# Opioid_-_IO_-_rev_A0.net
KiCad netlist of a schematic drawn in Altium Designer
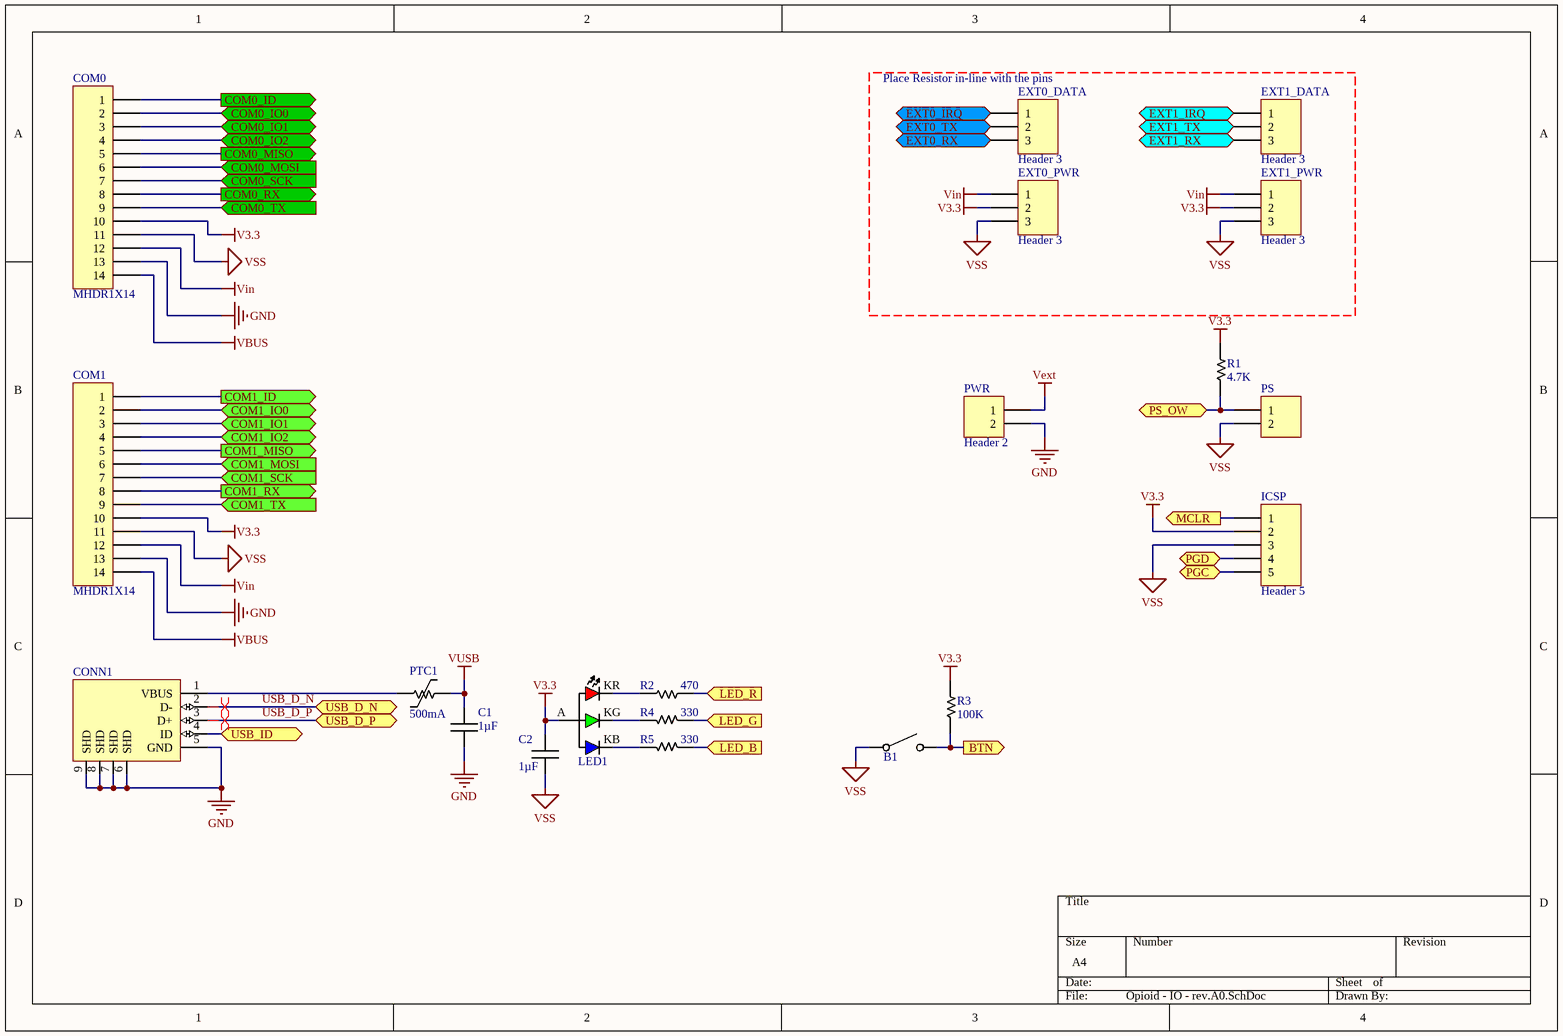
[diagram p0: Opioid - IO - rev.A0.SchDoc]

(export (version "E")
  (design (tool "Eeschema 10.0.6"))
  (components
    (comp (ref "B1")
      (value "Tact Button NO")
      (footprint "Tact TH 4pin 6×6mm")
      (libsource (lib "Megaxone") (part "Tact Button NO"))
    )
    (comp (ref "C1") (value "1µF") (footprint "CAPC1608N") (libsource (lib "Megaxone") (part "Capacitor")))
    (comp (ref "C2") (value "1µF") (footprint "CAPC1608N") (libsource (lib "Megaxone") (part "Capacitor")))
    (comp (ref "COM0")
      (value "MHDR1X14")
      (footprint "MHDR1X14")
      (description "Header, 14-Pin")
      (fields (field (name "PUBLISHER") "Altium Limited"))
      (libsource (lib "Miscellaneous Connectors") (part "MHDR1X14"))
    )
    (comp (ref "COM1")
      (value "MHDR1X14")
      (footprint "MHDR1X14")
      (description "Header, 14-Pin")
      (fields (field (name "PUBLISHER") "Altium Limited"))
      (libsource (lib "Miscellaneous Connectors") (part "MHDR1X14"))
    )
    (comp (ref "CONN1")
      (value "USB-Conn Mini-B SMD")
      (footprint "440478")
      (libsource (lib "Megaxone") (part "USB-Conn Mini-B SMD"))
    )
    (comp (ref "EXT0_DATA")
      (value "Header 3")
      (footprint "HDR1X3")
      (description "Header, 3-Pin")
      (fields (field (name "PUBLISHER") "Altium Limited"))
      (libsource (lib "Miscellaneous Connectors") (part "Header 3"))
    )
    (comp (ref "EXT0_PWR")
      (value "Header 3")
      (footprint "HDR1X3")
      (description "Header, 3-Pin")
      (fields (field (name "PUBLISHER") "Altium Limited"))
      (libsource (lib "Miscellaneous Connectors") (part "Header 3"))
    )
    (comp (ref "EXT1_DATA")
      (value "Header 3")
      (footprint "HDR1X3")
      (description "Header, 3-Pin")
      (fields (field (name "PUBLISHER") "Altium Limited"))
      (libsource (lib "Miscellaneous Connectors") (part "Header 3"))
    )
    (comp (ref "EXT1_PWR")
      (value "Header 3")
      (footprint "HDR1X3")
      (description "Header, 3-Pin")
      (fields (field (name "PUBLISHER") "Altium Limited"))
      (libsource (lib "Miscellaneous Connectors") (part "Header 3"))
    )
    (comp (ref "ICSP")
      (value "Header 5")
      (footprint "HDR1X5")
      (description "Header, 5-Pin")
      (fields (field (name "PUBLISHER") "Altium Limited"))
      (libsource (lib "Miscellaneous Connectors") (part "Header 5"))
    )
    (comp (ref "LED1")
      (value "LED RGB common A")
      (footprint "LED 3528m")
      (libsource (lib "Megaxone") (part "LED RGB common A"))
    )
    (comp (ref "PS")
      (value "MHDR1X2")
      (footprint "MHDR1X2")
      (description "Header, 2-Pin")
      (fields (field (name "PUBLISHER") "Altium Limited"))
      (libsource (lib "Miscellaneous Connectors") (part "MHDR1X2"))
    )
    (comp (ref "PTC1") (value "500mA") (footprint "RESC3225N") (libsource (lib "Megaxone") (part "PTC")))
    (comp (ref "PWR")
      (value "Header 2")
      (footprint "HDR1X2")
      (description "Header, 2-Pin")
      (fields (field (name "PUBLISHER") "Altium Limited"))
      (libsource (lib "Miscellaneous Connectors") (part "Header 2"))
    )
    (comp (ref "R1") (value "4.7K") (footprint "RESC1608N") (libsource (lib "") (part "Resistor_1")))
    (comp (ref "R2") (value "470") (footprint "RESC1608N") (libsource (lib "Megaxone") (part "Resistor")))
    (comp (ref "R3") (value "100K") (footprint "RESC1608N") (libsource (lib "") (part "Resistor_1")))
    (comp (ref "R4") (value "330") (footprint "RESC1608N") (libsource (lib "") (part "Resistor_1")))
    (comp (ref "R5") (value "330") (footprint "RESC1608N") (libsource (lib "") (part "Resistor_1")))
  )
  (nets
    (net (code "1") (name "/BTN") (class "Default")
      (node (ref "B1") (pin "2") (pinfunction "2_2") (pintype "passive"))
      (node (ref "R3") (pin "1") (pinfunction "1_1") (pintype "passive"))
    )
    (net (code "2") (name "/COM0_ID") (class "Default")
      (node (ref "COM0") (pin "1") (pinfunction "1_1") (pintype "passive"))
    )
    (net (code "3") (name "/COM0_IO0") (class "Default")
      (node (ref "COM0") (pin "2") (pinfunction "2_2") (pintype "passive"))
    )
    (net (code "4") (name "/COM0_IO1") (class "Default")
      (node (ref "COM0") (pin "3") (pinfunction "3_3") (pintype "passive"))
    )
    (net (code "5") (name "/COM0_IO2") (class "Default")
      (node (ref "COM0") (pin "4") (pinfunction "4_4") (pintype "passive"))
    )
    (net (code "6") (name "/COM0_MISO") (class "Default")
      (node (ref "COM0") (pin "5") (pinfunction "5_5") (pintype "passive"))
    )
    (net (code "7") (name "/COM0_MOSI") (class "Default")
      (node (ref "COM0") (pin "6") (pinfunction "6_6") (pintype "passive"))
    )
    (net (code "8") (name "/COM0_RX") (class "Default")
      (node (ref "COM0") (pin "8") (pinfunction "8_8") (pintype "passive"))
    )
    (net (code "9") (name "/COM0_SCK") (class "Default")
      (node (ref "COM0") (pin "7") (pinfunction "7_7") (pintype "passive"))
    )
    (net (code "10") (name "/COM0_TX") (class "Default")
      (node (ref "COM0") (pin "9") (pinfunction "9_9") (pintype "passive"))
    )
    (net (code "11") (name "/COM1_ID") (class "Default")
      (node (ref "COM1") (pin "1") (pinfunction "1_1") (pintype "passive"))
    )
    (net (code "12") (name "/COM1_IO0") (class "Default")
      (node (ref "COM1") (pin "2") (pinfunction "2_2") (pintype "passive"))
    )
    (net (code "13") (name "/COM1_IO1") (class "Default")
      (node (ref "COM1") (pin "3") (pinfunction "3_3") (pintype "passive"))
    )
    (net (code "14") (name "/COM1_IO2") (class "Default")
      (node (ref "COM1") (pin "4") (pinfunction "4_4") (pintype "passive"))
    )
    (net (code "15") (name "/COM1_MISO") (class "Default")
      (node (ref "COM1") (pin "5") (pinfunction "5_5") (pintype "passive"))
    )
    (net (code "16") (name "/COM1_MOSI") (class "Default")
      (node (ref "COM1") (pin "6") (pinfunction "6_6") (pintype "passive"))
    )
    (net (code "17") (name "/COM1_RX") (class "Default")
      (node (ref "COM1") (pin "8") (pinfunction "8_8") (pintype "passive"))
    )
    (net (code "18") (name "/COM1_SCK") (class "Default")
      (node (ref "COM1") (pin "7") (pinfunction "7_7") (pintype "passive"))
    )
    (net (code "19") (name "/COM1_TX") (class "Default")
      (node (ref "COM1") (pin "9") (pinfunction "9_9") (pintype "passive"))
    )
    (net (code "20") (name "/EXT0_IRQ") (class "Default")
      (node (ref "EXT0_DATA") (pin "1") (pinfunction "1_1") (pintype "passive"))
    )
    (net (code "21") (name "/EXT0_RX") (class "Default")
      (node (ref "EXT0_DATA") (pin "3") (pinfunction "3_3") (pintype "passive"))
    )
    (net (code "22") (name "/EXT0_TX") (class "Default")
      (node (ref "EXT0_DATA") (pin "2") (pinfunction "2_2") (pintype "passive"))
    )
    (net (code "23") (name "/EXT1_IRQ") (class "Default")
      (node (ref "EXT1_DATA") (pin "1") (pinfunction "1_1") (pintype "passive"))
    )
    (net (code "24") (name "/EXT1_RX") (class "Default")
      (node (ref "EXT1_DATA") (pin "3") (pinfunction "3_3") (pintype "passive"))
    )
    (net (code "25") (name "/EXT1_TX") (class "Default")
      (node (ref "EXT1_DATA") (pin "2") (pinfunction "2_2") (pintype "passive"))
    )
    (net (code "26") (name "/LED_B") (class "Default")
      (node (ref "R5") (pin "2") (pinfunction "2_2") (pintype "passive"))
    )
    (net (code "27") (name "/LED_G") (class "Default")
      (node (ref "R4") (pin "2") (pinfunction "2_2") (pintype "passive"))
    )
    (net (code "28") (name "/LED_R") (class "Default")
      (node (ref "R2") (pin "2") (pinfunction "2_2") (pintype "passive"))
    )
    (net (code "29") (name "/MCLR") (class "Default")
      (node (ref "ICSP") (pin "1") (pinfunction "1_1") (pintype "passive"))
    )
    (net (code "30") (name "/PGC") (class "Default")
      (node (ref "ICSP") (pin "5") (pinfunction "5_5") (pintype "passive"))
    )
    (net (code "31") (name "/PGD") (class "Default")
      (node (ref "ICSP") (pin "4") (pinfunction "4_4") (pintype "passive"))
    )
    (net (code "32") (name "/PS_OW") (class "Default")
      (node (ref "PS") (pin "1") (pinfunction "1_1") (pintype "passive"))
      (node (ref "R1") (pin "1") (pinfunction "1_1") (pintype "passive"))
    )
    (net (code "33") (name "/USB_D_N") (class "Default")
      (node (ref "CONN1") (pin "2") (pinfunction "D-_2") (pintype "bidirectional"))
    )
    (net (code "34") (name "/USB_D_P") (class "Default")
      (node (ref "CONN1") (pin "3") (pinfunction "D+_3") (pintype "bidirectional"))
    )
    (net (code "35") (name "/USB_ID") (class "Default")
      (node (ref "CONN1") (pin "4") (pinfunction "ID_4") (pintype "bidirectional"))
    )
    (net (code "36") (name "GND") (class "Default")
      (node (ref "C1") (pin "1") (pinfunction "1_1") (pintype "passive"))
      (node (ref "COM0") (pin "13") (pinfunction "13_13") (pintype "passive"))
      (node (ref "COM1") (pin "13") (pinfunction "13_13") (pintype "passive"))
      (node (ref "CONN1") (pin "5") (pinfunction "GND_5") (pintype "power_in"))
      (node (ref "CONN1") (pin "6") (pinfunction "SHD_6") (pintype "power_in"))
      (node (ref "CONN1") (pin "7") (pinfunction "SHD_7") (pintype "passive"))
      (node (ref "CONN1") (pin "8") (pinfunction "SHD_8") (pintype "passive"))
      (node (ref "CONN1") (pin "9") (pinfunction "SHD_9") (pintype "passive"))
      (node (ref "PWR") (pin "2") (pinfunction "2_2") (pintype "passive"))
    )
    (net (code "37") (name "Net-(CONN1-VBUS)") (class "Default")
      (node (ref "CONN1") (pin "1") (pinfunction "VBUS_1") (pintype "power_in"))
      (node (ref "PTC1") (pin "1") (pinfunction "1_1") (pintype "passive"))
    )
    (net (code "38") (name "Net-(LED1-PadKB)") (class "Default")
      (node (ref "LED1") (pin "KB") (pinfunction "KB_KB") (pintype "passive"))
      (node (ref "R5") (pin "1") (pinfunction "1_1") (pintype "passive"))
    )
    (net (code "39") (name "Net-(LED1-PadKG)") (class "Default")
      (node (ref "LED1") (pin "KG") (pinfunction "KG_KG") (pintype "passive"))
      (node (ref "R4") (pin "1") (pinfunction "1_1") (pintype "passive"))
    )
    (net (code "40") (name "Net-(LED1-PadKR)") (class "Default")
      (node (ref "LED1") (pin "KR") (pinfunction "KR_KR") (pintype "passive"))
      (node (ref "R2") (pin "1") (pinfunction "1_1") (pintype "passive"))
    )
    (net (code "41") (name "V3.3") (class "Default")
      (node (ref "C2") (pin "2") (pinfunction "2_2") (pintype "passive"))
      (node (ref "COM0") (pin "10") (pinfunction "10_10") (pintype "passive"))
      (node (ref "COM1") (pin "10") (pinfunction "10_10") (pintype "passive"))
      (node (ref "EXT0_PWR") (pin "2") (pinfunction "2_2") (pintype "passive"))
      (node (ref "EXT1_PWR") (pin "2") (pinfunction "2_2") (pintype "passive"))
      (node (ref "ICSP") (pin "2") (pinfunction "2_2") (pintype "passive"))
      (node (ref "LED1") (pin "A") (pinfunction "A_A") (pintype "passive"))
      (node (ref "R1") (pin "2") (pinfunction "2_2") (pintype "passive"))
      (node (ref "R3") (pin "2") (pinfunction "2_2") (pintype "passive"))
    )
    (net (code "42") (name "VBUS") (class "Default")
      (node (ref "COM0") (pin "14") (pinfunction "14_14") (pintype "passive"))
      (node (ref "COM1") (pin "14") (pinfunction "14_14") (pintype "passive"))
    )
    (net (code "43") (name "VSS") (class "Default")
      (node (ref "B1") (pin "1") (pinfunction "1_1") (pintype "passive"))
      (node (ref "C2") (pin "1") (pinfunction "1_1") (pintype "passive"))
      (node (ref "COM0") (pin "11") (pinfunction "11_11") (pintype "passive"))
      (node (ref "COM1") (pin "11") (pinfunction "11_11") (pintype "passive"))
      (node (ref "EXT0_PWR") (pin "3") (pinfunction "3_3") (pintype "passive"))
      (node (ref "EXT1_PWR") (pin "3") (pinfunction "3_3") (pintype "passive"))
      (node (ref "ICSP") (pin "3") (pinfunction "3_3") (pintype "passive"))
      (node (ref "PS") (pin "2") (pinfunction "2_2") (pintype "passive"))
    )
    (net (code "44") (name "VUSB") (class "Default")
      (node (ref "C1") (pin "2") (pinfunction "2_2") (pintype "passive"))
      (node (ref "PTC1") (pin "2") (pinfunction "2_2") (pintype "passive"))
    )
    (net (code "45") (name "Vext") (class "Default")
      (node (ref "PWR") (pin "1") (pinfunction "1_1") (pintype "passive"))
    )
    (net (code "46") (name "Vin") (class "Default")
      (node (ref "COM0") (pin "12") (pinfunction "12_12") (pintype "passive"))
      (node (ref "COM1") (pin "12") (pinfunction "12_12") (pintype "passive"))
      (node (ref "EXT0_PWR") (pin "1") (pinfunction "1_1") (pintype "passive"))
      (node (ref "EXT1_PWR") (pin "1") (pinfunction "1_1") (pintype "passive"))
    )
  )
)
